# HMIInterface.net
KiCad netlist of a schematic drawn in Altium Designer
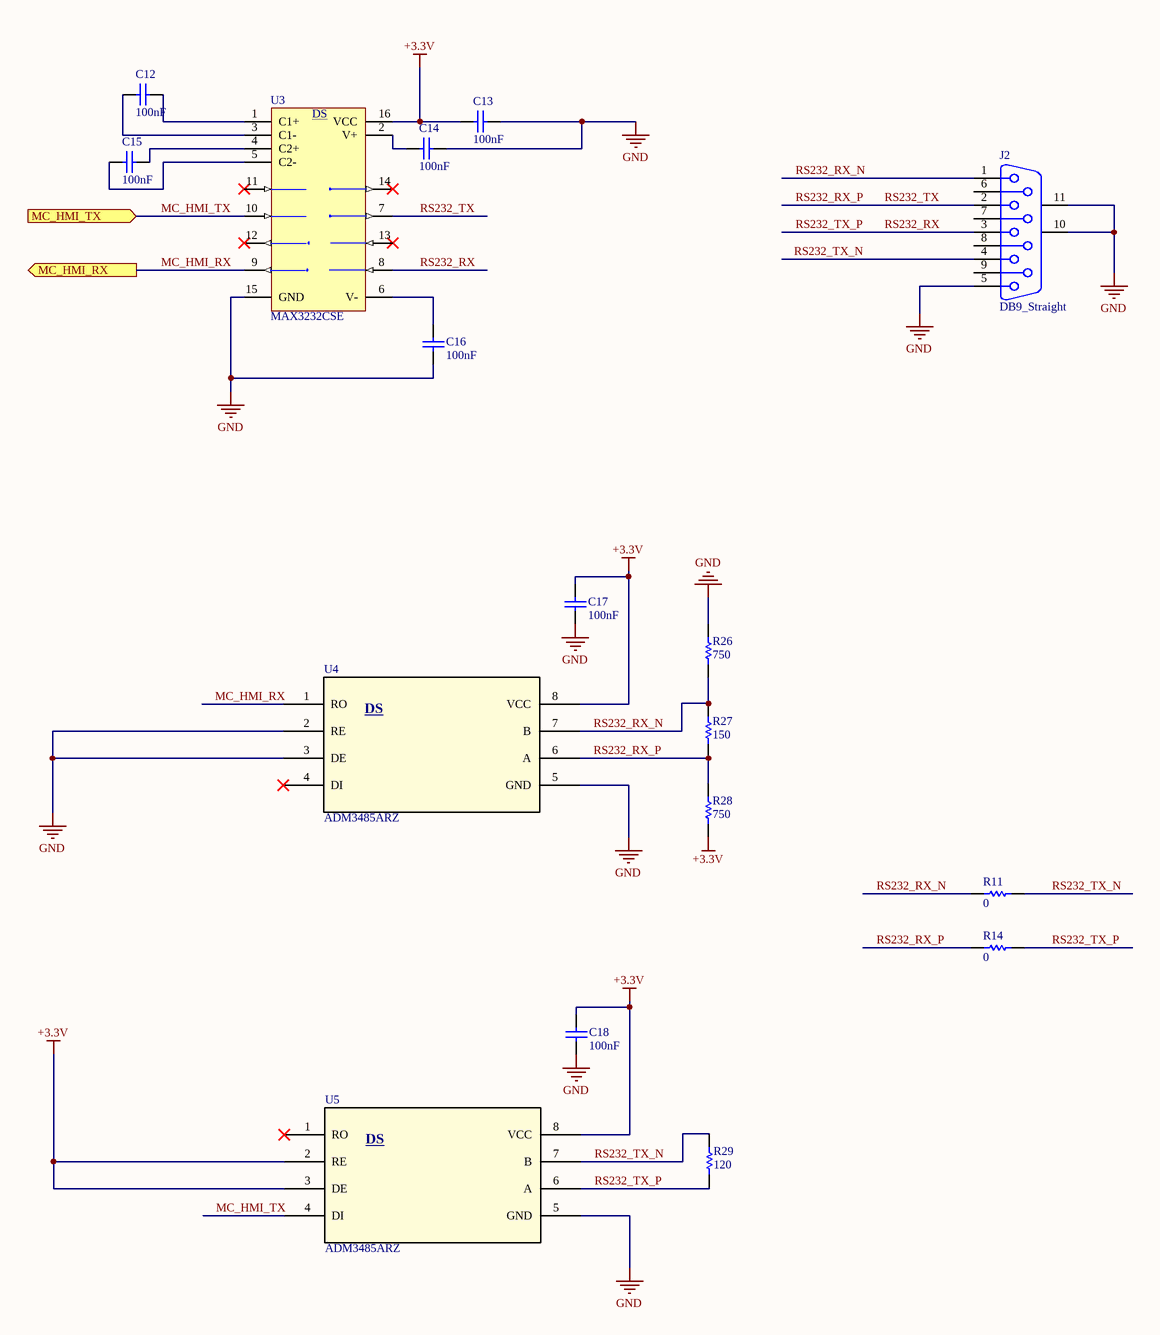
[diagram p0: HMIInterface.SchDoc]

(export (version "E")
  (design (tool "Eeschema 10.0.6"))
  (components
    (comp (ref "C12")
      (value "100nF")
      (footprint "C-805")
      (description "Capacitor")
      (fields (field (name "Comment") "C-805") (field (name "PUBLISHER") "Altium Limited"))
      (libsource (lib "AfraLIB") (part "C-805"))
    )
    (comp (ref "C13")
      (value "100nF")
      (footprint "C-805")
      (description "Capacitor")
      (fields (field (name "Comment") "C-805") (field (name "PUBLISHER") "Altium Limited"))
      (libsource (lib "AfraLIB") (part "C-805"))
    )
    (comp (ref "C14")
      (value "100nF")
      (footprint "C-805")
      (description "Capacitor")
      (fields (field (name "Comment") "C-805") (field (name "PUBLISHER") "Altium Limited"))
      (libsource (lib "AfraLIB") (part "C-805"))
    )
    (comp (ref "C15")
      (value "100nF")
      (footprint "C-805")
      (description "Capacitor")
      (fields (field (name "Comment") "C-805") (field (name "PUBLISHER") "Altium Limited"))
      (libsource (lib "AfraLIB") (part "C-805"))
    )
    (comp (ref "C16")
      (value "100nF")
      (footprint "C-805")
      (description "Capacitor")
      (fields (field (name "Comment") "C-805") (field (name "PUBLISHER") "Altium Limited"))
      (libsource (lib "AfraLIB") (part "C-805"))
    )
    (comp (ref "C17")
      (value "100nF")
      (footprint "C-805")
      (description "Capacitor")
      (fields (field (name "Comment") "C-805") (field (name "PUBLISHER") "Altium Limited"))
      (libsource (lib "AfraLIB") (part "C-805"))
    )
    (comp (ref "C18")
      (value "100nF")
      (footprint "C-805")
      (description "Capacitor")
      (fields (field (name "Comment") "C-805") (field (name "PUBLISHER") "Altium Limited"))
      (libsource (lib "AfraLIB") (part "C-805"))
    )
    (comp (ref "J2")
      (value "DB9_Straight")
      (footprint "DB9_Straight")
      (description "Receptacle Assembly, 9 Position, Right Angle")
      (fields (field (name "PUBLISHER") "Altium Limited"))
      (libsource (lib "AfraLIB") (part "DB9_Straight"))
    )
    (comp (ref "R11")
      (value "0")
      (footprint "R-805")
      (description "Resistor")
      (fields (field (name "Comment") "R-805"))
      (libsource (lib "AfraLIB") (part "R-805"))
    )
    (comp (ref "R14")
      (value "0")
      (footprint "R-805")
      (description "Resistor")
      (fields (field (name "Comment") "R-805"))
      (libsource (lib "AfraLIB") (part "R-805"))
    )
    (comp (ref "R26")
      (value "750")
      (footprint "R-805")
      (description "Resistor")
      (fields (field (name "Comment") "R-805"))
      (libsource (lib "AfraLIB") (part "R-805"))
    )
    (comp (ref "R27")
      (value "150")
      (footprint "R-805")
      (description "Resistor")
      (fields (field (name "Comment") "R-805"))
      (libsource (lib "AfraLIB") (part "R-805"))
    )
    (comp (ref "R28")
      (value "750")
      (footprint "R-805")
      (description "Resistor")
      (fields (field (name "Comment") "R-805"))
      (libsource (lib "AfraLIB") (part "R-805"))
    )
    (comp (ref "R29")
      (value "120")
      (footprint "R-805")
      (description "Resistor")
      (fields (field (name "Comment") "R-805"))
      (libsource (lib "AfraLIB") (part "R-805"))
    )
    (comp (ref "U3")
      (value "MAX3232CSE")
      (footprint "MAX3232CSE")
      (description "3.0V TO 5.5V, Low-Power, up to 1Mbps, True RS-232 Transceiver Using Four 0.1µF External Capacitor")
      (fields (field (name "PUBLISHER") "Altium Limited"))
      (libsource (lib "AfraLIB") (part "MAX3232CSE"))
    )
    (comp (ref "U4")
      (value "ADM3485ARZ")
      (footprint "R_8")
      (description "No Description Available")
      (fields (field (name "COPYRIGHT") "Copyright (C) 2018 Accelerated Designs. All rights reserved"))
      (libsource (lib "AfraLIB") (part "ADM3485ARZ"))
    )
    (comp (ref "U5")
      (value "ADM3485ARZ")
      (footprint "R_8")
      (description "No Description Available")
      (fields (field (name "COPYRIGHT") "Copyright (C) 2018 Accelerated Designs. All rights reserved"))
      (libsource (lib "AfraLIB") (part "ADM3485ARZ"))
    )
  )
  (nets
    (net (code "1") (name "+3.3V") (class "Default")
      (node (ref "C13") (pin "2") (pinfunction "2_2") (pintype "passive"))
      (node (ref "C17") (pin "2") (pinfunction "2_2") (pintype "passive"))
      (node (ref "C18") (pin "2") (pinfunction "2_2") (pintype "passive"))
      (node (ref "R28") (pin "1") (pinfunction "1_1") (pintype "passive"))
      (node (ref "U3") (pin "16") (pinfunction "VCC_16") (pintype "power_in"))
      (node (ref "U4") (pin "8") (pinfunction "VCC_8") (pintype "passive"))
      (node (ref "U5") (pin "2") (pinfunction "RE_2") (pintype "passive"))
      (node (ref "U5") (pin "3") (pinfunction "DE_3") (pintype "passive"))
      (node (ref "U5") (pin "8") (pinfunction "VCC_8") (pintype "passive"))
    )
    (net (code "2") (name "/MC_HMI_RX") (class "Default")
      (node (ref "U3") (pin "9") (pinfunction "R2OUT_9") (pintype "output"))
      (node (ref "U4") (pin "1") (pinfunction "RO_1") (pintype "passive"))
    )
    (net (code "3") (name "/MC_HMI_TX") (class "Default")
      (node (ref "U3") (pin "10") (pinfunction "T2IN_10") (pintype "input"))
      (node (ref "U5") (pin "4") (pinfunction "DI_4") (pintype "passive"))
    )
    (net (code "4") (name "/RS232_RX") (class "Default")
      (node (ref "J2") (pin "3") (pinfunction "3_3") (pintype "passive"))
      (node (ref "R14") (pin "1") (pinfunction "1_1") (pintype "passive"))
      (node (ref "R29") (pin "1") (pinfunction "1_1") (pintype "passive"))
      (node (ref "U3") (pin "8") (pinfunction "R2IN_8") (pintype "input"))
      (node (ref "U5") (pin "6") (pinfunction "A_6") (pintype "passive"))
    )
    (net (code "5") (name "/RS232_RX_N") (class "Default")
      (node (ref "J2") (pin "1") (pinfunction "1_1") (pintype "passive"))
      (node (ref "R11") (pin "2") (pinfunction "2_2") (pintype "passive"))
      (node (ref "R26") (pin "1") (pinfunction "1_1") (pintype "passive"))
      (node (ref "R27") (pin "2") (pinfunction "2_2") (pintype "passive"))
      (node (ref "U4") (pin "7") (pinfunction "B_7") (pintype "passive"))
    )
    (net (code "6") (name "/RS232_RX_P") (class "Default")
      (node (ref "J2") (pin "2") (pinfunction "2_2") (pintype "passive"))
      (node (ref "R14") (pin "2") (pinfunction "2_2") (pintype "passive"))
      (node (ref "R27") (pin "1") (pinfunction "1_1") (pintype "passive"))
      (node (ref "R28") (pin "2") (pinfunction "2_2") (pintype "passive"))
      (node (ref "U3") (pin "7") (pinfunction "T2OUT_7") (pintype "output"))
      (node (ref "U4") (pin "6") (pinfunction "A_6") (pintype "passive"))
    )
    (net (code "7") (name "/RS232_TX_N") (class "Default")
      (node (ref "J2") (pin "4") (pinfunction "4_4") (pintype "passive"))
      (node (ref "R11") (pin "1") (pinfunction "1_1") (pintype "passive"))
      (node (ref "R29") (pin "2") (pinfunction "2_2") (pintype "passive"))
      (node (ref "U5") (pin "7") (pinfunction "B_7") (pintype "passive"))
    )
    (net (code "8") (name "GND") (class "Default")
      (node (ref "C13") (pin "1") (pinfunction "1_1") (pintype "passive"))
      (node (ref "C14") (pin "1") (pinfunction "1_1") (pintype "passive"))
      (node (ref "C16") (pin "1") (pinfunction "1_1") (pintype "passive"))
      (node (ref "C17") (pin "1") (pinfunction "1_1") (pintype "passive"))
      (node (ref "C18") (pin "1") (pinfunction "1_1") (pintype "passive"))
      (node (ref "J2") (pin "10") (pinfunction "MH1_10") (pintype "passive"))
      (node (ref "J2") (pin "11") (pinfunction "MH2_11") (pintype "passive"))
      (node (ref "J2") (pin "5") (pinfunction "5_5") (pintype "passive"))
      (node (ref "R26") (pin "2") (pinfunction "2_2") (pintype "passive"))
      (node (ref "U3") (pin "15") (pinfunction "GND_15") (pintype "power_in"))
      (node (ref "U4") (pin "2") (pinfunction "RE_2") (pintype "passive"))
      (node (ref "U4") (pin "3") (pinfunction "DE_3") (pintype "passive"))
      (node (ref "U4") (pin "5") (pinfunction "GND_5") (pintype "passive"))
      (node (ref "U5") (pin "5") (pinfunction "GND_5") (pintype "passive"))
    )
    (net (code "9") (name "Net-(U3-C1+)") (class "Default")
      (node (ref "C12") (pin "1") (pinfunction "1_1") (pintype "passive"))
      (node (ref "U3") (pin "1") (pinfunction "C1+_1") (pintype "passive"))
    )
    (net (code "10") (name "Net-(U3-C1-)") (class "Default")
      (node (ref "C12") (pin "2") (pinfunction "2_2") (pintype "passive"))
      (node (ref "U3") (pin "3") (pinfunction "C1-_3") (pintype "passive"))
    )
    (net (code "11") (name "Net-(U3-C2+)") (class "Default")
      (node (ref "C15") (pin "1") (pinfunction "1_1") (pintype "passive"))
      (node (ref "U3") (pin "4") (pinfunction "C2+_4") (pintype "passive"))
    )
    (net (code "12") (name "Net-(U3-C2-)") (class "Default")
      (node (ref "C15") (pin "2") (pinfunction "2_2") (pintype "passive"))
      (node (ref "U3") (pin "5") (pinfunction "C2-_5") (pintype "passive"))
    )
    (net (code "13") (name "Net-(U3-V+)") (class "Default")
      (node (ref "C14") (pin "2") (pinfunction "2_2") (pintype "passive"))
      (node (ref "U3") (pin "2") (pinfunction "V+_2") (pintype "power_in"))
    )
    (net (code "14") (name "Net-(U3-V-)") (class "Default")
      (node (ref "C16") (pin "2") (pinfunction "2_2") (pintype "passive"))
      (node (ref "U3") (pin "6") (pinfunction "V-_6") (pintype "power_in"))
    )
    (net (code "15") (name "unconnected-(J2-Pad6)") (class "Default")
      (node (ref "J2") (pin "6") (pinfunction "6_6") (pintype "passive"))
    )
    (net (code "16") (name "unconnected-(J2-Pad7)") (class "Default")
      (node (ref "J2") (pin "7") (pinfunction "7_7") (pintype "passive"))
    )
    (net (code "17") (name "unconnected-(J2-Pad8)") (class "Default")
      (node (ref "J2") (pin "8") (pinfunction "8_8") (pintype "passive"))
    )
    (net (code "18") (name "unconnected-(J2-Pad9)") (class "Default")
      (node (ref "J2") (pin "9") (pinfunction "9_9") (pintype "passive"))
    )
    (net (code "19") (name "unconnected-(U3-R1IN-Pad13)") (class "Default")
      (node (ref "U3") (pin "13") (pinfunction "R1IN_13") (pintype "input+no_connect"))
    )
    (net (code "20") (name "unconnected-(U3-R1OUT-Pad12)") (class "Default")
      (node (ref "U3") (pin "12") (pinfunction "R1OUT_12") (pintype "output+no_connect"))
    )
    (net (code "21") (name "unconnected-(U3-T1IN-Pad11)") (class "Default")
      (node (ref "U3") (pin "11") (pinfunction "T1IN_11") (pintype "input+no_connect"))
    )
    (net (code "22") (name "unconnected-(U3-T1OUT-Pad14)") (class "Default")
      (node (ref "U3") (pin "14") (pinfunction "T1OUT_14") (pintype "output+no_connect"))
    )
    (net (code "23") (name "unconnected-(U4-DI-Pad4)") (class "Default")
      (node (ref "U4") (pin "4") (pinfunction "DI_4") (pintype "passive+no_connect"))
    )
    (net (code "24") (name "unconnected-(U5-RO-Pad1)") (class "Default")
      (node (ref "U5") (pin "1") (pinfunction "RO_1") (pintype "passive+no_connect"))
    )
  )
)
